# Wifi-controller.net
KiCad netlist of a schematic drawn in EasyEDA Pro
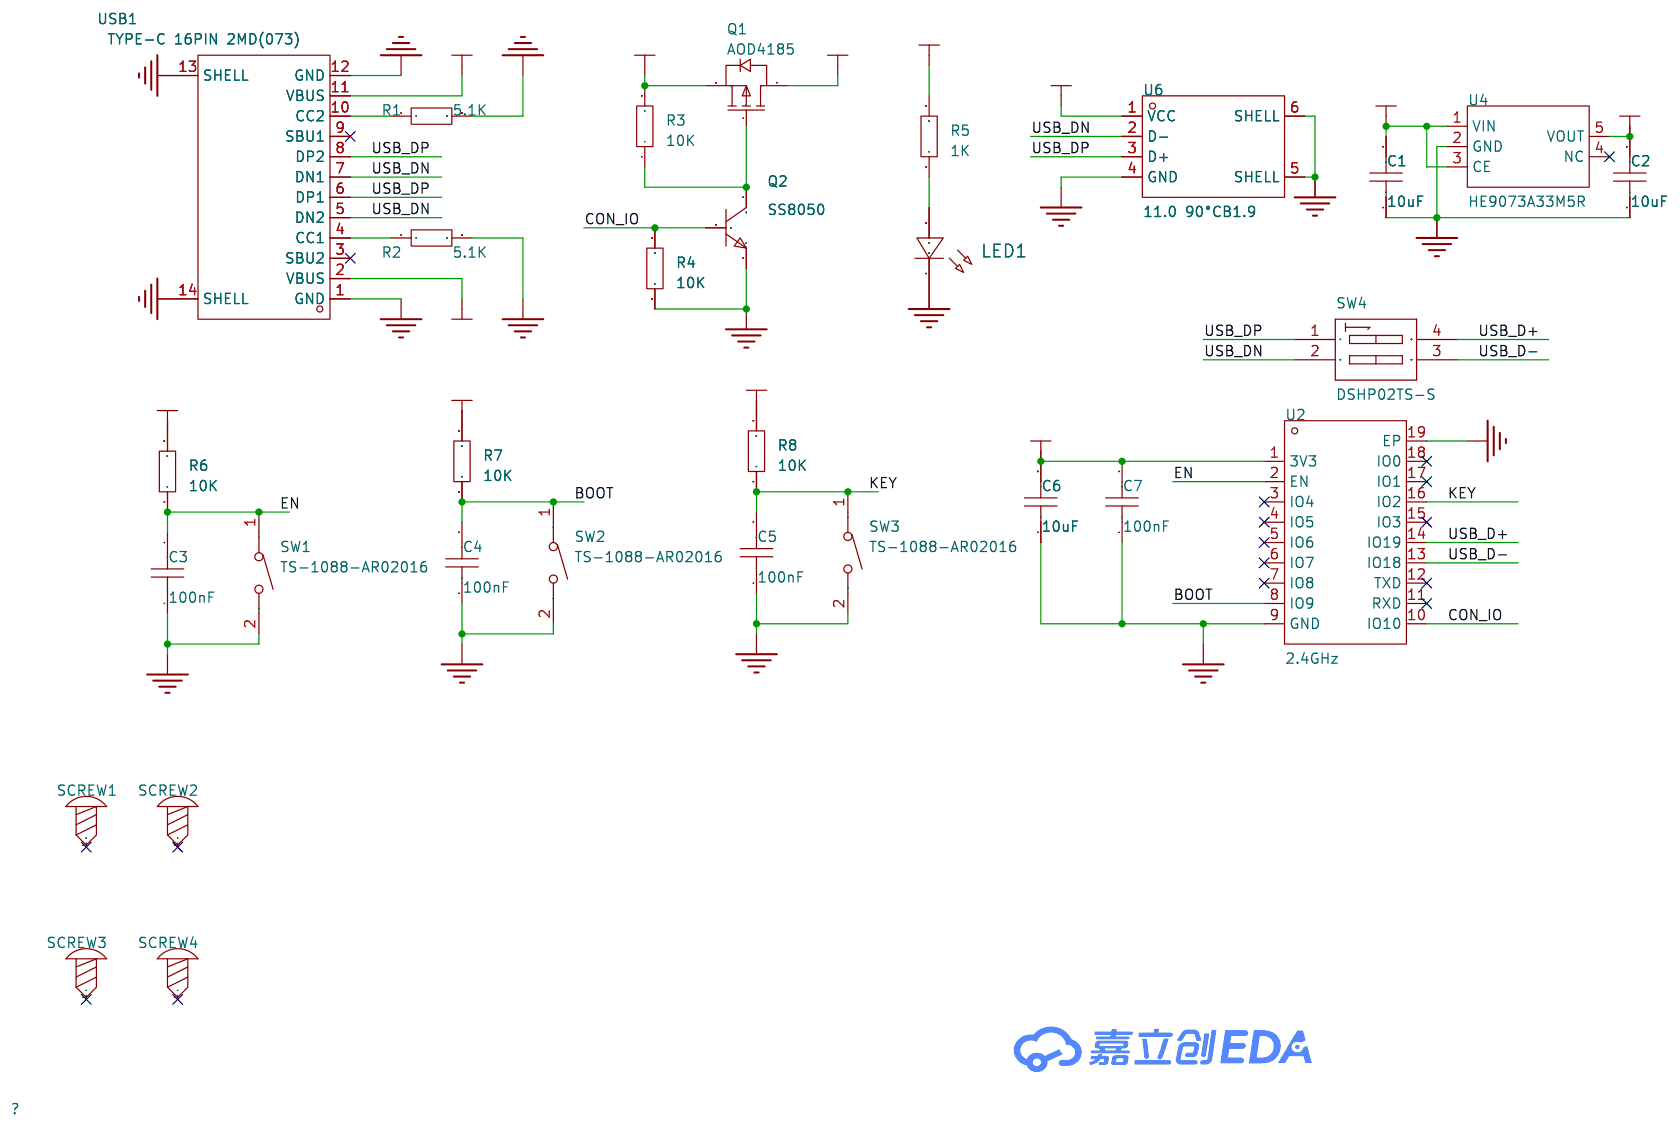
[diagram p0: schematic sheet]

(export (version "E")
  (design (tool "Eeschema 10.0.6"))
  (components
    (comp (ref "C1")
      (value "10uF")
      (footprint "easyedapro:C0603")
      (libsource (lib "easyedapro") (part "CapAcitance"))
    )
    (comp (ref "C2")
      (value "10uF")
      (footprint "easyedapro:C0603")
      (libsource (lib "easyedapro") (part "CapAcitance"))
    )
    (comp (ref "C3")
      (value "100nF")
      (footprint "easyedapro:C0603")
      (libsource (lib "easyedapro") (part "CapAcitance"))
    )
    (comp (ref "C4")
      (value "100nF")
      (footprint "easyedapro:C0603")
      (libsource (lib "easyedapro") (part "CapAcitance"))
    )
    (comp (ref "C5")
      (value "100nF")
      (footprint "easyedapro:C0603")
      (libsource (lib "easyedapro") (part "CapAcitance"))
    )
    (comp (ref "C6")
      (value "10uF")
      (footprint "easyedapro:C0603")
      (libsource (lib "easyedapro") (part "CapAcitance"))
    )
    (comp (ref "C7")
      (value "100nF")
      (footprint "easyedapro:C0603")
      (libsource (lib "easyedapro") (part "CapAcitance"))
    )
    (comp (ref "LED1")
      (value "~")
      (footprint "easyedapro:LED_0603")
      (libsource (lib "easyedapro") (part "LED_R"))
    )
    (comp (ref "Q1")
      (value "AOD4185")
      (footprint "easyedapro:TO-252-3_L6.6-W6.1-P4.57-LS9.9-BR-CW")
      (fields (field (name "Manufacturer") "AOS"))
      (libsource (lib "easyedapro") (part "AOD4185_C400894"))
    )
    (comp (ref "Q2")
      (value "SS8050")
      (footprint "easyedapro:SOT-23-3_L2.9-W1.3-P1.90-LS2.4-BR")
      (description "晶体管类型:NPN;集电极电流(Ic):1.5A;集射极击穿电压(Vceo):25V;耗散功率(Pd):300mW;直流电流增益(hFE):120@100mA,1.0V;")
      (fields (field (name "Manufacturer") "宏嘉诚"))
      (libsource (lib "easyedapro") (part "SS8050_C7420370"))
    )
    (comp (ref "R1") (value "5.1K") (footprint "easyedapro:R0603") (libsource (lib "easyedapro") (part "电阻")))
    (comp (ref "R2") (value "5.1K") (footprint "easyedapro:R0603") (libsource (lib "easyedapro") (part "电阻")))
    (comp (ref "R3") (value "10K") (footprint "easyedapro:R0603") (libsource (lib "easyedapro") (part "电阻")))
    (comp (ref "R4") (value "10K") (footprint "easyedapro:R0603") (libsource (lib "easyedapro") (part "电阻")))
    (comp (ref "R5") (value "1K") (footprint "easyedapro:R0603") (libsource (lib "easyedapro") (part "电阻")))
    (comp (ref "R6") (value "10K") (footprint "easyedapro:R0603") (libsource (lib "easyedapro") (part "电阻")))
    (comp (ref "R7") (value "10K") (footprint "easyedapro:R0603") (libsource (lib "easyedapro") (part "电阻")))
    (comp (ref "R8") (value "10K") (footprint "easyedapro:R0603") (libsource (lib "easyedapro") (part "电阻")))
    (comp (ref "SCREW1")
      (value "~")
      (footprint "easyedapro:M3螺丝")
      (libsource (lib "easyedapro") (part "螺丝孔"))
    )
    (comp (ref "SCREW2")
      (value "~")
      (footprint "easyedapro:M3螺丝")
      (libsource (lib "easyedapro") (part "螺丝孔"))
    )
    (comp (ref "SCREW3")
      (value "~")
      (footprint "easyedapro:M3螺丝")
      (libsource (lib "easyedapro") (part "螺丝孔"))
    )
    (comp (ref "SCREW4")
      (value "~")
      (footprint "easyedapro:M3螺丝")
      (libsource (lib "easyedapro") (part "螺丝孔"))
    )
    (comp (ref "SW1")
      (value "TS-1088-AR02016")
      (footprint "easyedapro:SW-SMD_L3.9-W3.0-P4.45")
      (fields (field (name "Manufacturer") "XUNPU(讯普)"))
      (libsource (lib "easyedapro") (part "TS-1088-AR02016"))
    )
    (comp (ref "SW2")
      (value "TS-1088-AR02016")
      (footprint "easyedapro:SW-SMD_L3.9-W3.0-P4.45")
      (fields (field (name "Manufacturer") "XUNPU(讯普)"))
      (libsource (lib "easyedapro") (part "TS-1088-AR02016"))
    )
    (comp (ref "SW3")
      (value "TS-1088-AR02016")
      (footprint "easyedapro:SW-SMD_L3.9-W3.0-P4.45")
      (fields (field (name "Manufacturer") "XUNPU(讯普)"))
      (libsource (lib "easyedapro") (part "TS-1088-AR02016"))
    )
    (comp (ref "SW4")
      (value "DSHP02TS-S")
      (footprint "easyedapro:SW-SMD_DSHP02TS-S_1")
      (description "类型:平拨,凹槽式;电路结构:单刀单掷;开关位数:2位;额定电流:25mA;额定电压:24V;使用寿命:3千次;颜色:黑色;")
      (fields (field (name "Manufacturer") "XKB Connectivity(中国星坤)"))
      (libsource (lib "easyedapro") (part "DSHP02TS-S"))
    )
    (comp (ref "U2")
      (value "2.4GHz")
      (footprint "easyedapro:BULETM-SMD_ESPRESSIF_ESP32-C3-WROOM-02-N4-4MB")
      (description "核心处理器:ESP32-C3芯片;频率:2.4GHz;发射功率:20.5dBm;")
      (fields
        (field (name "Manufacturer Part") "ESP32-C3-WROOM-02-N4")
        (field (name "Manufacturer") "ESPRESSIF(乐鑫)")
      )
      (libsource (lib "easyedapro") (part "ESP32-C3-WROOM-02-N4(4MB)"))
    )
    (comp (ref "U4")
      (value "HE9073A33M5R")
      (footprint "easyedapro:SOT-23-5_L3.0-W1.7-P0.95-LS2.8-BL")
      (description "输出类型:固定;工作电压:7V;输出电压:3.3V;输出电流:500mA;电源纹波抑制比(PSRR):70dB@(1kHz);输出极性:正极;")
      (fields (field (name "Manufacturer") "HEERMICR(赫尔半导体)"))
      (libsource (lib "easyedapro") (part "HE9073A33M5R"))
    )
    (comp (ref "U6")
      (value "11.0 90°CB1.9")
      (footprint "easyedapro:USB-A-TH_905-761A2022D10201")
      (description "连接器类型:Type-A;标准:USB 2.0;公母:母;安装方式:沉板;触点数量:4P;端口数量:1;额定电流 - 电源:1.5A;工作温度范围:-25°C~+85°C;")
      (fields (field (name "Manufacturer") "SHOU HAN(首韩)"))
      (libsource (lib "easyedapro") (part "11.0 90°CB1.9"))
    )
    (comp (ref "USB1")
      (value "TYPE-C 16PIN 2MD(073)")
      (footprint "easyedapro:USB-C-SMD_TYPE-C-6PIN-2MD-073")
      (description "连接器类型:Type-C;标准:USB 3.1;公母:母;安装方式:卧贴;触点数量:16P;端口数量:1;额定电流 - 电源:5A;工作温度范围:-25°C~+85°C;")
      (fields (field (name "Manufacturer") "SHOU HAN(首韩)"))
      (libsource (lib "easyedapro") (part "TYPE-C 16PIN 2MD(073)"))
    )
  )
  (nets
    (net (code "1") (name "+3.3V") (class "Default")
      (node (ref "C2") (pin "2") (pinfunction "2_2") (pintype "input"))
      (node (ref "C6") (pin "2") (pinfunction "2_2") (pintype "input"))
      (node (ref "C7") (pin "2") (pinfunction "2_2") (pintype "input"))
      (node (ref "R6") (pin "2") (pinfunction "2_2") (pintype "input"))
      (node (ref "R7") (pin "2") (pinfunction "2_2") (pintype "input"))
      (node (ref "R8") (pin "2") (pinfunction "2_2") (pintype "input"))
      (node (ref "U2") (pin "1") (pinfunction "3V3_1") (pintype "unspecified"))
      (node (ref "U4") (pin "5") (pinfunction "VOUT_5") (pintype "unspecified"))
    )
    (net (code "2") (name "/BOOT") (class "Default")
      (node (ref "C4") (pin "2") (pinfunction "2_2") (pintype "input"))
      (node (ref "R7") (pin "1") (pinfunction "1_1") (pintype "input"))
      (node (ref "SW2") (pin "1") (pinfunction "1_1") (pintype "unspecified"))
      (node (ref "U2") (pin "8") (pinfunction "IO9_8") (pintype "unspecified"))
    )
    (net (code "3") (name "/CON_IO") (class "Default")
      (node (ref "Q2") (pin "1") (pinfunction "B_1") (pintype "input"))
      (node (ref "R4") (pin "2") (pinfunction "2_2") (pintype "input"))
      (node (ref "U2") (pin "10") (pinfunction "IO10_10") (pintype "unspecified"))
    )
    (net (code "4") (name "/EN") (class "Default")
      (node (ref "C3") (pin "2") (pinfunction "2_2") (pintype "input"))
      (node (ref "R6") (pin "1") (pinfunction "1_1") (pintype "input"))
      (node (ref "SW1") (pin "1") (pinfunction "1_1") (pintype "unspecified"))
      (node (ref "U2") (pin "2") (pinfunction "EN_2") (pintype "unspecified"))
    )
    (net (code "5") (name "/KEY") (class "Default")
      (node (ref "C5") (pin "2") (pinfunction "2_2") (pintype "input"))
      (node (ref "R8") (pin "1") (pinfunction "1_1") (pintype "input"))
      (node (ref "SW3") (pin "1") (pinfunction "1_1") (pintype "unspecified"))
      (node (ref "U2") (pin "16") (pinfunction "IO2_16") (pintype "unspecified"))
    )
    (net (code "6") (name "/USB_D+") (class "Default")
      (node (ref "SW4") (pin "4") (pinfunction "B1_4") (pintype "input"))
      (node (ref "U2") (pin "14") (pinfunction "IO19_14") (pintype "unspecified"))
    )
    (net (code "7") (name "/USB_D-") (class "Default")
      (node (ref "SW4") (pin "3") (pinfunction "B2_3") (pintype "input"))
      (node (ref "U2") (pin "13") (pinfunction "IO18_13") (pintype "unspecified"))
    )
    (net (code "8") (name "/USB_DN") (class "Default")
      (node (ref "SW4") (pin "2") (pinfunction "A2_2") (pintype "input"))
      (node (ref "U6") (pin "2") (pinfunction "D-_2") (pintype "unspecified"))
      (node (ref "USB1") (pin "5") (pinfunction "DN2_5") (pintype "unspecified"))
      (node (ref "USB1") (pin "7") (pinfunction "DN1_7") (pintype "unspecified"))
    )
    (net (code "9") (name "/USB_DP") (class "Default")
      (node (ref "SW4") (pin "1") (pinfunction "A1_1") (pintype "input"))
      (node (ref "U6") (pin "3") (pinfunction "D+_3") (pintype "unspecified"))
      (node (ref "USB1") (pin "6") (pinfunction "DP1_6") (pintype "unspecified"))
      (node (ref "USB1") (pin "8") (pinfunction "DP2_8") (pintype "unspecified"))
    )
    (net (code "10") (name "GND") (class "Default")
      (node (ref "C1") (pin "1") (pinfunction "1_1") (pintype "input"))
      (node (ref "C2") (pin "1") (pinfunction "1_1") (pintype "input"))
      (node (ref "C3") (pin "1") (pinfunction "1_1") (pintype "input"))
      (node (ref "C4") (pin "1") (pinfunction "1_1") (pintype "input"))
      (node (ref "C5") (pin "1") (pinfunction "1_1") (pintype "input"))
      (node (ref "C6") (pin "1") (pinfunction "1_1") (pintype "input"))
      (node (ref "C7") (pin "1") (pinfunction "1_1") (pintype "input"))
      (node (ref "LED1") (pin "1") (pinfunction "C_1") (pintype "input"))
      (node (ref "Q2") (pin "2") (pinfunction "E_2") (pintype "input"))
      (node (ref "R1") (pin "2") (pinfunction "2_2") (pintype "input"))
      (node (ref "R2") (pin "2") (pinfunction "2_2") (pintype "input"))
      (node (ref "R4") (pin "1") (pinfunction "1_1") (pintype "input"))
      (node (ref "SW1") (pin "2") (pinfunction "2_2") (pintype "unspecified"))
      (node (ref "SW2") (pin "2") (pinfunction "2_2") (pintype "unspecified"))
      (node (ref "SW3") (pin "2") (pinfunction "2_2") (pintype "unspecified"))
      (node (ref "U2") (pin "19") (pinfunction "EP_19") (pintype "unspecified"))
      (node (ref "U2") (pin "9") (pinfunction "GND_9") (pintype "unspecified"))
      (node (ref "U4") (pin "2") (pinfunction "GND_2") (pintype "unspecified"))
      (node (ref "U6") (pin "4") (pinfunction "GND_4") (pintype "unspecified"))
      (node (ref "U6") (pin "5") (pinfunction "SHELL_5") (pintype "unspecified"))
      (node (ref "U6") (pin "6") (pinfunction "SHELL_6") (pintype "unspecified"))
      (node (ref "USB1") (pin "1") (pinfunction "GND_1") (pintype "unspecified"))
      (node (ref "USB1") (pin "12") (pinfunction "GND_12") (pintype "unspecified"))
      (node (ref "USB1") (pin "13") (pinfunction "SHELL_13") (pintype "unspecified"))
      (node (ref "USB1") (pin "14") (pinfunction "SHELL_14") (pintype "unspecified"))
    )
    (net (code "11") (name "Net-(LED1-A)") (class "Default")
      (node (ref "LED1") (pin "2") (pinfunction "A_2") (pintype "input"))
      (node (ref "R5") (pin "1") (pinfunction "1_1") (pintype "input"))
    )
    (net (code "12") (name "Net-(Q1-G)") (class "Default")
      (node (ref "Q1") (pin "1") (pinfunction "G_1") (pintype "unspecified"))
      (node (ref "Q2") (pin "3") (pinfunction "C_3") (pintype "input"))
      (node (ref "R3") (pin "1") (pinfunction "1_1") (pintype "input"))
    )
    (net (code "13") (name "Net-(USB1-CC1)") (class "Default")
      (node (ref "R2") (pin "1") (pinfunction "1_1") (pintype "input"))
      (node (ref "USB1") (pin "4") (pinfunction "CC1_4") (pintype "unspecified"))
    )
    (net (code "14") (name "Net-(USB1-CC2)") (class "Default")
      (node (ref "R1") (pin "1") (pinfunction "1_1") (pintype "input"))
      (node (ref "USB1") (pin "10") (pinfunction "CC2_10") (pintype "unspecified"))
    )
    (net (code "15") (name "VIN") (class "Default")
      (node (ref "C1") (pin "2") (pinfunction "2_2") (pintype "input"))
      (node (ref "Q1") (pin "3") (pinfunction "S_3") (pintype "unspecified"))
      (node (ref "R3") (pin "2") (pinfunction "2_2") (pintype "input"))
      (node (ref "U4") (pin "1") (pinfunction "VIN_1") (pintype "unspecified"))
      (node (ref "U4") (pin "3") (pinfunction "CE_3") (pintype "unspecified"))
      (node (ref "USB1") (pin "11") (pinfunction "VBUS_11") (pintype "unspecified"))
      (node (ref "USB1") (pin "2") (pinfunction "VBUS_2") (pintype "unspecified"))
    )
    (net (code "16") (name "VOUT") (class "Default")
      (node (ref "Q1") (pin "2") (pinfunction "D_2") (pintype "unspecified"))
      (node (ref "R5") (pin "2") (pinfunction "2_2") (pintype "input"))
      (node (ref "U6") (pin "1") (pinfunction "VCC_1") (pintype "unspecified"))
    )
    (net (code "17") (name "unconnected-(SCREW1-Pad1)") (class "Default")
      (node (ref "SCREW1") (pin "1") (pinfunction "1_1") (pintype "input+no_connect"))
    )
    (net (code "18") (name "unconnected-(SCREW2-Pad1)") (class "Default")
      (node (ref "SCREW2") (pin "1") (pinfunction "1_1") (pintype "input+no_connect"))
    )
    (net (code "19") (name "unconnected-(SCREW3-Pad1)") (class "Default")
      (node (ref "SCREW3") (pin "1") (pinfunction "1_1") (pintype "input+no_connect"))
    )
    (net (code "20") (name "unconnected-(SCREW4-Pad1)") (class "Default")
      (node (ref "SCREW4") (pin "1") (pinfunction "1_1") (pintype "input+no_connect"))
    )
    (net (code "21") (name "unconnected-(U2-IO0-Pad18)") (class "Default")
      (node (ref "U2") (pin "18") (pinfunction "IO0_18") (pintype "unspecified+no_connect"))
    )
    (net (code "22") (name "unconnected-(U2-IO1-Pad17)") (class "Default")
      (node (ref "U2") (pin "17") (pinfunction "IO1_17") (pintype "unspecified+no_connect"))
    )
    (net (code "23") (name "unconnected-(U2-IO3-Pad15)") (class "Default")
      (node (ref "U2") (pin "15") (pinfunction "IO3_15") (pintype "unspecified+no_connect"))
    )
    (net (code "24") (name "unconnected-(U2-IO4-Pad3)") (class "Default")
      (node (ref "U2") (pin "3") (pinfunction "IO4_3") (pintype "unspecified+no_connect"))
    )
    (net (code "25") (name "unconnected-(U2-IO5-Pad4)") (class "Default")
      (node (ref "U2") (pin "4") (pinfunction "IO5_4") (pintype "unspecified+no_connect"))
    )
    (net (code "26") (name "unconnected-(U2-IO6-Pad5)") (class "Default")
      (node (ref "U2") (pin "5") (pinfunction "IO6_5") (pintype "unspecified+no_connect"))
    )
    (net (code "27") (name "unconnected-(U2-IO7-Pad6)") (class "Default")
      (node (ref "U2") (pin "6") (pinfunction "IO7_6") (pintype "unspecified+no_connect"))
    )
    (net (code "28") (name "unconnected-(U2-IO8-Pad7)") (class "Default")
      (node (ref "U2") (pin "7") (pinfunction "IO8_7") (pintype "unspecified+no_connect"))
    )
    (net (code "29") (name "unconnected-(U2-RXD-Pad11)") (class "Default")
      (node (ref "U2") (pin "11") (pinfunction "RXD_11") (pintype "unspecified+no_connect"))
    )
    (net (code "30") (name "unconnected-(U2-TXD-Pad12)") (class "Default")
      (node (ref "U2") (pin "12") (pinfunction "TXD_12") (pintype "unspecified+no_connect"))
    )
    (net (code "31") (name "unconnected-(U4-NC-Pad4)") (class "Default")
      (node (ref "U4") (pin "4") (pinfunction "NC_4") (pintype "unspecified+no_connect"))
    )
    (net (code "32") (name "unconnected-(USB1-SBU1-Pad9)") (class "Default")
      (node (ref "USB1") (pin "9") (pinfunction "SBU1_9") (pintype "unspecified+no_connect"))
    )
    (net (code "33") (name "unconnected-(USB1-SBU2-Pad3)") (class "Default")
      (node (ref "USB1") (pin "3") (pinfunction "SBU2_3") (pintype "unspecified+no_connect"))
    )
  )
)
